# pin_matrix.net
KiCad netlist of a schematic drawn in EAGLE
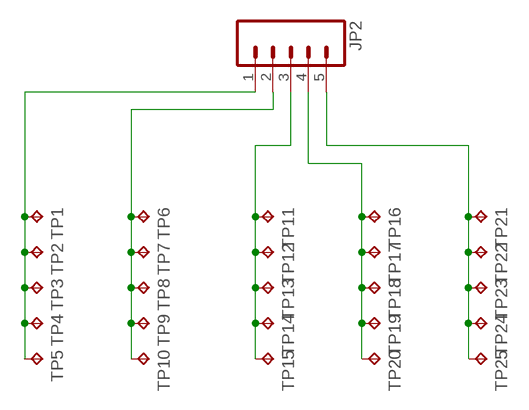
[diagram p0: schematic, sheet 1]

(export (version "E")
  (design (tool "Eeschema 10.0.6"))
  (components
    (comp (ref "JP2")
      (value "M05PTH")
      (footprint "eagle-import:1X05")
      (libsource (lib "eagle-import") (part "M05PTH"))
    )
    (comp (ref "TP1")
      (value "TPPAD1-20")
      (footprint "eagle-import:P1-20")
      (libsource (lib "eagle-import") (part "TPPAD1-20"))
    )
    (comp (ref "TP2")
      (value "TPPAD1-20")
      (footprint "eagle-import:P1-20")
      (libsource (lib "eagle-import") (part "TPPAD1-20"))
    )
    (comp (ref "TP3")
      (value "TPPAD1-20")
      (footprint "eagle-import:P1-20")
      (libsource (lib "eagle-import") (part "TPPAD1-20"))
    )
    (comp (ref "TP4")
      (value "TPPAD1-20")
      (footprint "eagle-import:P1-20")
      (libsource (lib "eagle-import") (part "TPPAD1-20"))
    )
    (comp (ref "TP5")
      (value "TPPAD1-20")
      (footprint "eagle-import:P1-20")
      (libsource (lib "eagle-import") (part "TPPAD1-20"))
    )
    (comp (ref "TP6")
      (value "TPPAD1-20")
      (footprint "eagle-import:P1-20")
      (libsource (lib "eagle-import") (part "TPPAD1-20"))
    )
    (comp (ref "TP7")
      (value "TPPAD1-20")
      (footprint "eagle-import:P1-20")
      (libsource (lib "eagle-import") (part "TPPAD1-20"))
    )
    (comp (ref "TP8")
      (value "TPPAD1-20")
      (footprint "eagle-import:P1-20")
      (libsource (lib "eagle-import") (part "TPPAD1-20"))
    )
    (comp (ref "TP9")
      (value "TPPAD1-20")
      (footprint "eagle-import:P1-20")
      (libsource (lib "eagle-import") (part "TPPAD1-20"))
    )
    (comp (ref "TP10")
      (value "TPPAD1-20")
      (footprint "eagle-import:P1-20")
      (libsource (lib "eagle-import") (part "TPPAD1-20"))
    )
    (comp (ref "TP11")
      (value "TPPAD1-20")
      (footprint "eagle-import:P1-20")
      (libsource (lib "eagle-import") (part "TPPAD1-20"))
    )
    (comp (ref "TP12")
      (value "TPPAD1-20")
      (footprint "eagle-import:P1-20")
      (libsource (lib "eagle-import") (part "TPPAD1-20"))
    )
    (comp (ref "TP13")
      (value "TPPAD1-20")
      (footprint "eagle-import:P1-20")
      (libsource (lib "eagle-import") (part "TPPAD1-20"))
    )
    (comp (ref "TP14")
      (value "TPPAD1-20")
      (footprint "eagle-import:P1-20")
      (libsource (lib "eagle-import") (part "TPPAD1-20"))
    )
    (comp (ref "TP15")
      (value "TPPAD1-20")
      (footprint "eagle-import:P1-20")
      (libsource (lib "eagle-import") (part "TPPAD1-20"))
    )
    (comp (ref "TP16")
      (value "TPPAD1-20")
      (footprint "eagle-import:P1-20")
      (libsource (lib "eagle-import") (part "TPPAD1-20"))
    )
    (comp (ref "TP17")
      (value "TPPAD1-20")
      (footprint "eagle-import:P1-20")
      (libsource (lib "eagle-import") (part "TPPAD1-20"))
    )
    (comp (ref "TP18")
      (value "TPPAD1-20")
      (footprint "eagle-import:P1-20")
      (libsource (lib "eagle-import") (part "TPPAD1-20"))
    )
    (comp (ref "TP19")
      (value "TPPAD1-20")
      (footprint "eagle-import:P1-20")
      (libsource (lib "eagle-import") (part "TPPAD1-20"))
    )
    (comp (ref "TP20")
      (value "TPPAD1-20")
      (footprint "eagle-import:P1-20")
      (libsource (lib "eagle-import") (part "TPPAD1-20"))
    )
    (comp (ref "TP21")
      (value "TPPAD1-20")
      (footprint "eagle-import:P1-20")
      (libsource (lib "eagle-import") (part "TPPAD1-20"))
    )
    (comp (ref "TP22")
      (value "TPPAD1-20")
      (footprint "eagle-import:P1-20")
      (libsource (lib "eagle-import") (part "TPPAD1-20"))
    )
    (comp (ref "TP23")
      (value "TPPAD1-20")
      (footprint "eagle-import:P1-20")
      (libsource (lib "eagle-import") (part "TPPAD1-20"))
    )
    (comp (ref "TP24")
      (value "TPPAD1-20")
      (footprint "eagle-import:P1-20")
      (libsource (lib "eagle-import") (part "TPPAD1-20"))
    )
    (comp (ref "TP25")
      (value "TPPAD1-20")
      (footprint "eagle-import:P1-20")
      (libsource (lib "eagle-import") (part "TPPAD1-20"))
    )
  )
  (nets
    (net (code "1") (name "Net-(JP2-Pad1)") (class "Default")
      (node (ref "JP2") (pin "1") (pinfunction "1_1") (pintype "passive"))
      (node (ref "TP1") (pin "TP") (pinfunction "TP_TP") (pintype "input"))
      (node (ref "TP2") (pin "TP") (pinfunction "TP_TP") (pintype "input"))
      (node (ref "TP3") (pin "TP") (pinfunction "TP_TP") (pintype "input"))
      (node (ref "TP4") (pin "TP") (pinfunction "TP_TP") (pintype "input"))
      (node (ref "TP5") (pin "TP") (pinfunction "TP_TP") (pintype "input"))
    )
    (net (code "2") (name "Net-(JP2-Pad2)") (class "Default")
      (node (ref "JP2") (pin "2") (pinfunction "2_2") (pintype "passive"))
      (node (ref "TP10") (pin "TP") (pinfunction "TP_TP") (pintype "input"))
      (node (ref "TP6") (pin "TP") (pinfunction "TP_TP") (pintype "input"))
      (node (ref "TP7") (pin "TP") (pinfunction "TP_TP") (pintype "input"))
      (node (ref "TP8") (pin "TP") (pinfunction "TP_TP") (pintype "input"))
      (node (ref "TP9") (pin "TP") (pinfunction "TP_TP") (pintype "input"))
    )
    (net (code "3") (name "Net-(JP2-Pad3)") (class "Default")
      (node (ref "JP2") (pin "3") (pinfunction "3_3") (pintype "passive"))
      (node (ref "TP11") (pin "TP") (pinfunction "TP_TP") (pintype "input"))
      (node (ref "TP12") (pin "TP") (pinfunction "TP_TP") (pintype "input"))
      (node (ref "TP13") (pin "TP") (pinfunction "TP_TP") (pintype "input"))
      (node (ref "TP14") (pin "TP") (pinfunction "TP_TP") (pintype "input"))
      (node (ref "TP15") (pin "TP") (pinfunction "TP_TP") (pintype "input"))
    )
    (net (code "4") (name "Net-(JP2-Pad4)") (class "Default")
      (node (ref "JP2") (pin "4") (pinfunction "4_4") (pintype "passive"))
      (node (ref "TP16") (pin "TP") (pinfunction "TP_TP") (pintype "input"))
      (node (ref "TP17") (pin "TP") (pinfunction "TP_TP") (pintype "input"))
      (node (ref "TP18") (pin "TP") (pinfunction "TP_TP") (pintype "input"))
      (node (ref "TP19") (pin "TP") (pinfunction "TP_TP") (pintype "input"))
      (node (ref "TP20") (pin "TP") (pinfunction "TP_TP") (pintype "input"))
    )
    (net (code "5") (name "Net-(JP2-Pad5)") (class "Default")
      (node (ref "JP2") (pin "5") (pinfunction "5_5") (pintype "passive"))
      (node (ref "TP21") (pin "TP") (pinfunction "TP_TP") (pintype "input"))
      (node (ref "TP22") (pin "TP") (pinfunction "TP_TP") (pintype "input"))
      (node (ref "TP23") (pin "TP") (pinfunction "TP_TP") (pintype "input"))
      (node (ref "TP24") (pin "TP") (pinfunction "TP_TP") (pintype "input"))
      (node (ref "TP25") (pin "TP") (pinfunction "TP_TP") (pintype "input"))
    )
  )
)
